# xtValveTimer.net
KiCad netlist of a schematic drawn in EasyEDA
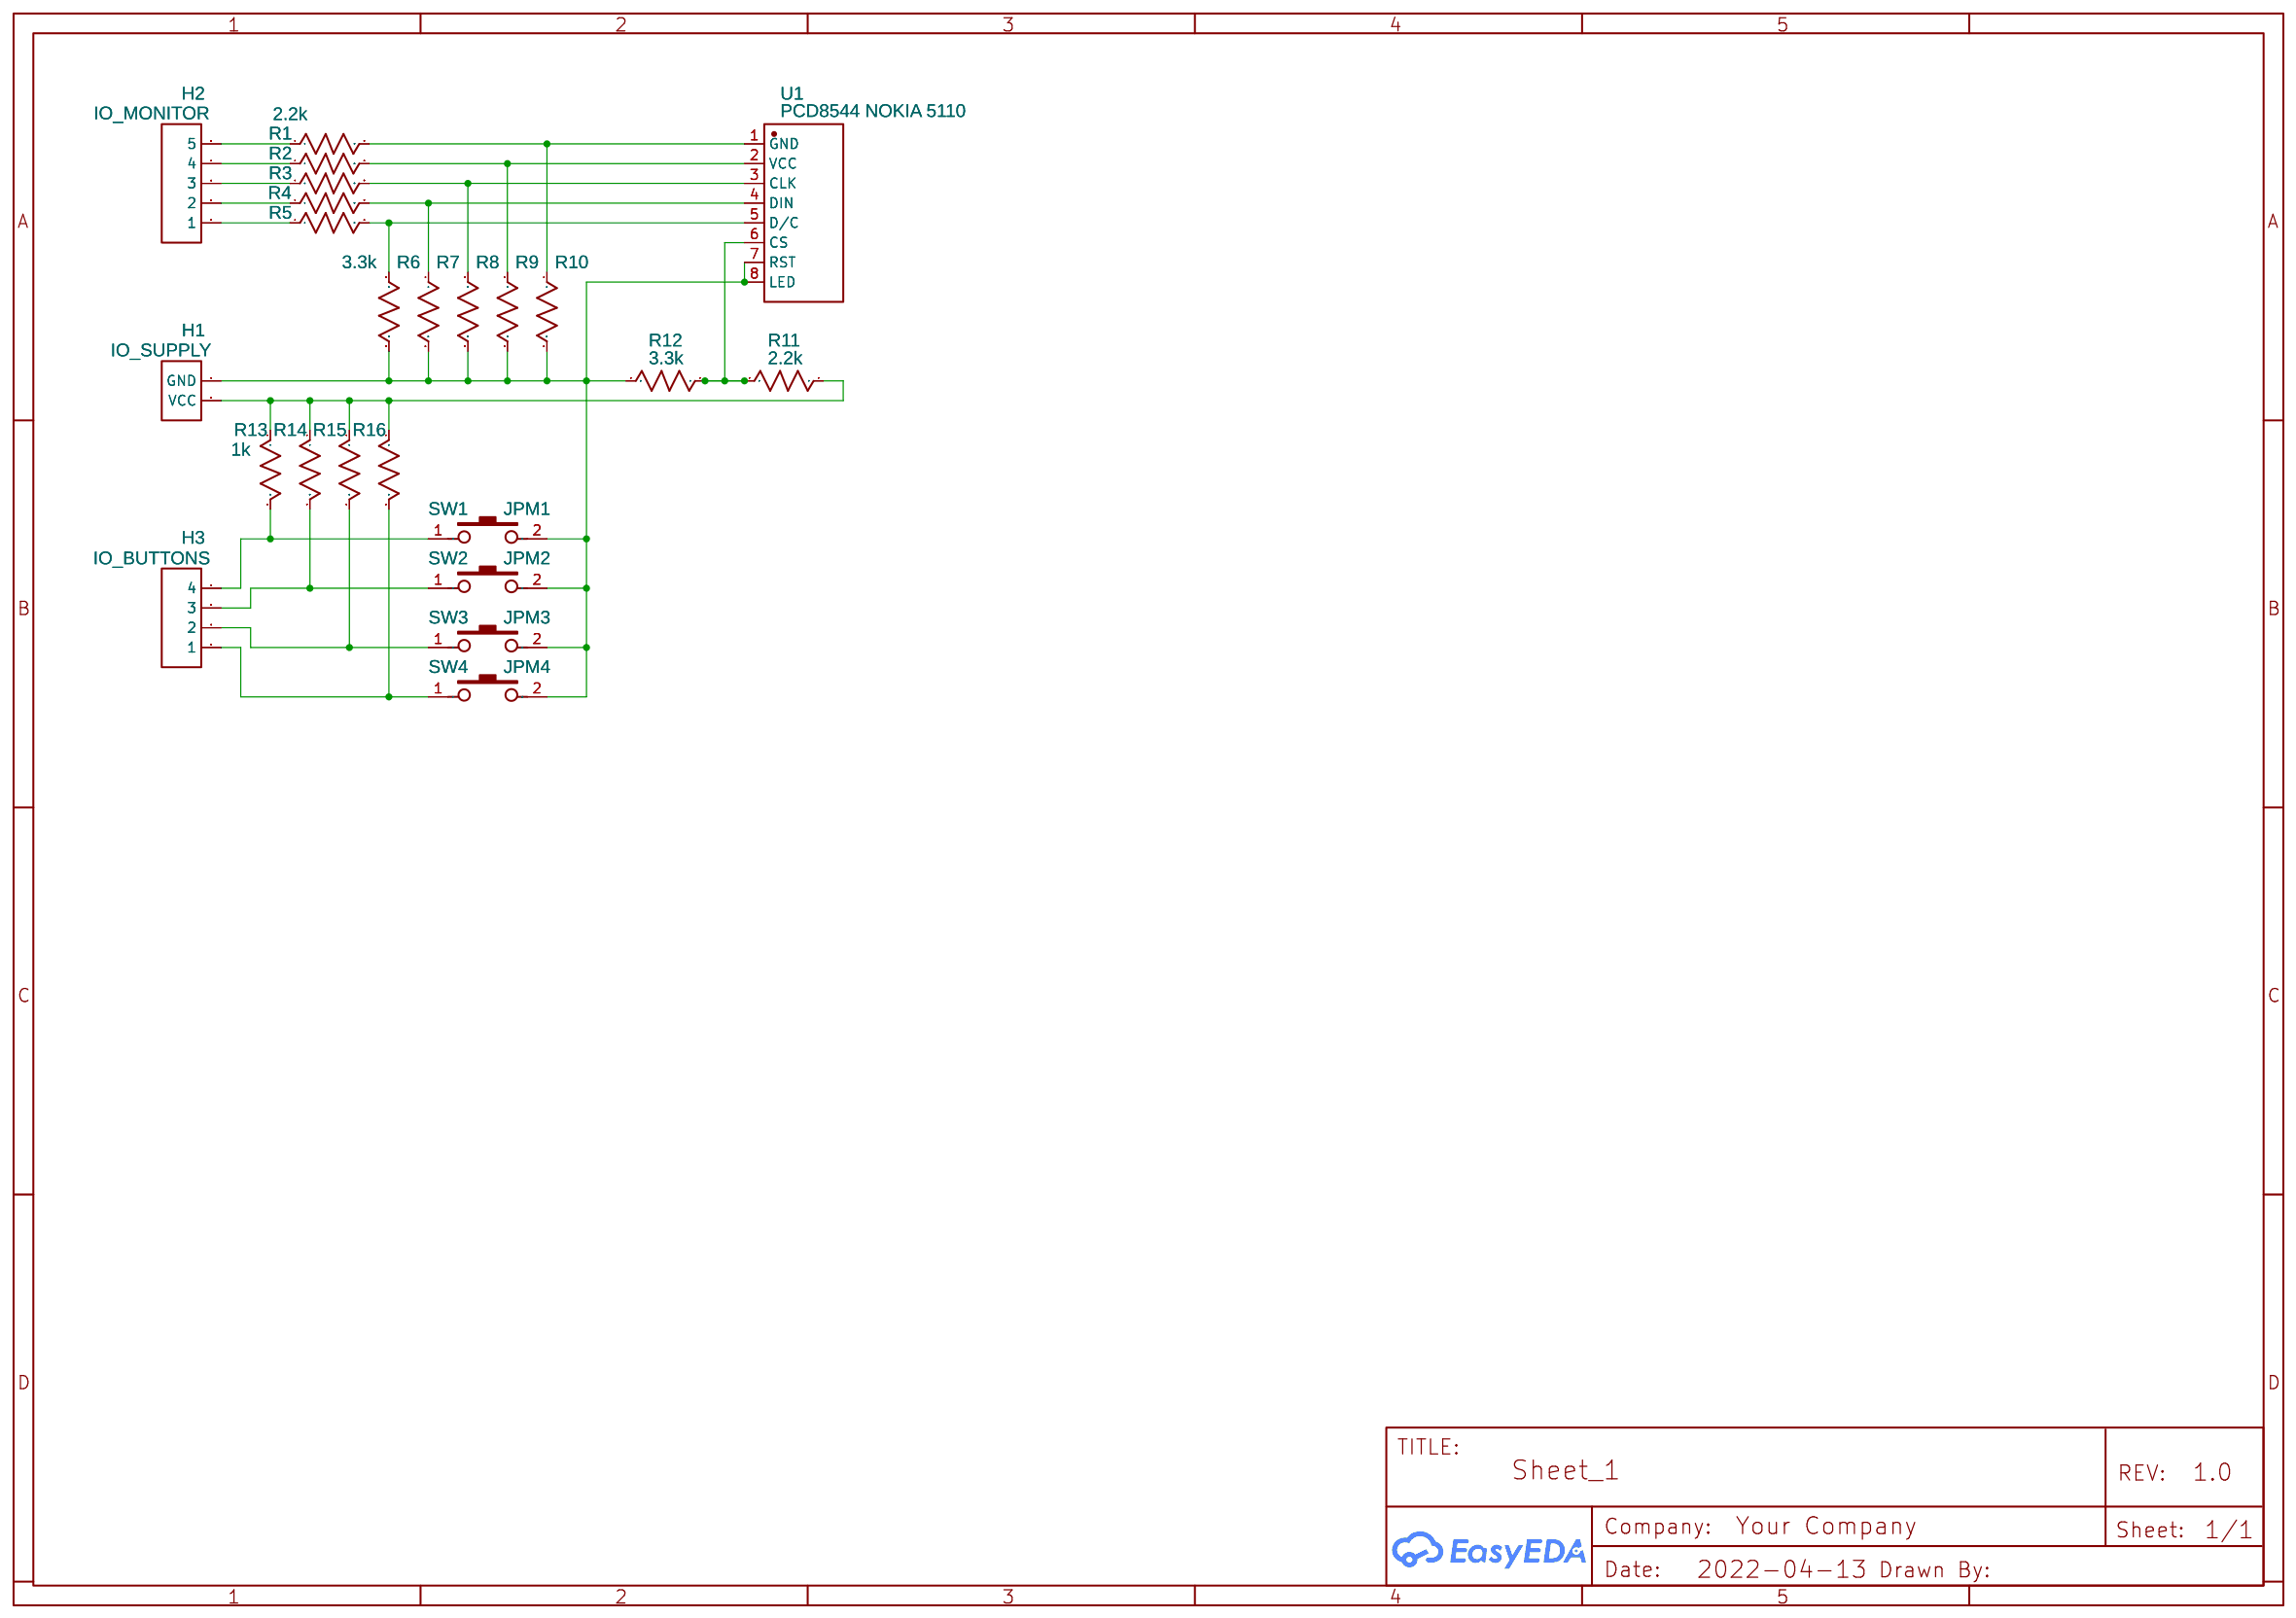
[diagram p0: schematic sheet]

(export (version "E")
  (design (tool "Eeschema 10.0.6"))
  (components
    (comp (ref "H1")
      (value "IO_SUPPLY")
      (fields (field (name "BOM_Supplier Part") "C49661"))
      (libsource (lib "") (part "HDR-F-2.54_1x2"))
    )
    (comp (ref "H2")
      (value "IO_MONITOR")
      (fields (field (name "BOM_Supplier Part") "C50950"))
      (libsource (lib "") (part "HDR-F-2.54_1x5"))
    )
    (comp (ref "H3")
      (value "IO_BUTTONS")
      (fields (field (name "BOM_Supplier Part") "C225501"))
      (libsource (lib "") (part "HDR-F-2.54_1x4"))
    )
    (comp (ref "R1") (value "2.2k") (libsource (lib "") (part "R_0603_US_2")))
    (comp (ref "R2") (value "1k") (libsource (lib "") (part "R_0603_US_2")))
    (comp (ref "R3") (value "1k") (libsource (lib "") (part "R_0603_US_2")))
    (comp (ref "R4") (value "1k") (libsource (lib "") (part "R_0603_US_2")))
    (comp (ref "R5") (value "1k") (libsource (lib "") (part "R_0603_US_2")))
    (comp (ref "R6") (value "3.3k") (libsource (lib "") (part "R_0603_US_1")))
    (comp (ref "R7") (value "3.3k") (libsource (lib "") (part "R_0603_US_1")))
    (comp (ref "R8") (value "3.3k") (libsource (lib "") (part "R_0603_US_1")))
    (comp (ref "R9") (value "3.3k") (libsource (lib "") (part "R_0603_US_1")))
    (comp (ref "R10") (value "3.3k") (libsource (lib "") (part "R_0603_US_1")))
    (comp (ref "R11") (value "2.2k") (libsource (lib "") (part "R_0603_US_3")))
    (comp (ref "R12") (value "3.3k") (libsource (lib "") (part "R_0603_US_3")))
    (comp (ref "R13") (value "1k") (libsource (lib "") (part "R_0603_US")))
    (comp (ref "R14") (value "1k") (libsource (lib "") (part "R_0603_US")))
    (comp (ref "R15") (value "1k") (libsource (lib "") (part "R_0603_US")))
    (comp (ref "R16") (value "1k") (libsource (lib "") (part "R_0603_US")))
    (comp (ref "SW1")
      (value "JPM1")
      (fields
        (field (name "BOM_Manufacturer Part") "JPM1040-2013FC")
        (field (name "BOM_Supplier Part") "C516061")
      )
      (libsource (lib "") (part "JPM1040-2013FC"))
    )
    (comp (ref "SW2")
      (value "JPM2")
      (fields
        (field (name "BOM_Manufacturer Part") "JPM1040-2013FC")
        (field (name "BOM_Supplier Part") "C516061")
      )
      (libsource (lib "") (part "JPM1040-2013FC"))
    )
    (comp (ref "SW3")
      (value "JPM3")
      (fields
        (field (name "BOM_Manufacturer Part") "JPM1040-2013FC")
        (field (name "BOM_Supplier Part") "C516061")
      )
      (libsource (lib "") (part "JPM1040-2013FC"))
    )
    (comp (ref "SW4")
      (value "JPM4")
      (fields
        (field (name "BOM_Manufacturer Part") "JPM1040-2013FC")
        (field (name "BOM_Supplier Part") "C516061")
      )
      (libsource (lib "") (part "JPM1040-2013FC"))
    )
    (comp (ref "U1") (value "PCD8544 NOKIA 5110") (libsource (lib "") (part "PCD8544 NOKIA 5110")))
  )
  (nets
    (net (code "1") (name "Net-(H1-GND)") (class "Default")
      (node (ref "H1") (pin "2") (pinfunction "GND_2") (pintype "input"))
      (node (ref "R10") (pin "2") (pinfunction "2_2") (pintype "unspecified"))
      (node (ref "R12") (pin "2") (pinfunction "2_2") (pintype "unspecified"))
      (node (ref "R6") (pin "2") (pinfunction "2_2") (pintype "unspecified"))
      (node (ref "R7") (pin "2") (pinfunction "2_2") (pintype "unspecified"))
      (node (ref "R8") (pin "2") (pinfunction "2_2") (pintype "unspecified"))
      (node (ref "R9") (pin "2") (pinfunction "2_2") (pintype "unspecified"))
      (node (ref "SW1") (pin "2") (pinfunction "2_2") (pintype "input"))
      (node (ref "SW2") (pin "2") (pinfunction "2_2") (pintype "input"))
      (node (ref "SW3") (pin "2") (pinfunction "2_2") (pintype "input"))
      (node (ref "SW4") (pin "2") (pinfunction "2_2") (pintype "input"))
      (node (ref "U1") (pin "7") (pinfunction "RST_7") (pintype "unspecified"))
      (node (ref "U1") (pin "8") (pinfunction "LED_8") (pintype "unspecified"))
    )
    (net (code "2") (name "Net-(H1-VCC)") (class "Default")
      (node (ref "H1") (pin "1") (pinfunction "VCC_1") (pintype "input"))
      (node (ref "R11") (pin "1") (pinfunction "1_1") (pintype "unspecified"))
      (node (ref "R13") (pin "1") (pinfunction "1_1") (pintype "unspecified"))
      (node (ref "R14") (pin "1") (pinfunction "1_1") (pintype "unspecified"))
      (node (ref "R15") (pin "1") (pinfunction "1_1") (pintype "unspecified"))
      (node (ref "R16") (pin "1") (pinfunction "1_1") (pintype "unspecified"))
    )
    (net (code "3") (name "Net-(H2-Pad1)") (class "Default")
      (node (ref "H2") (pin "1") (pinfunction "1_1") (pintype "unspecified"))
      (node (ref "R5") (pin "1") (pinfunction "1_1") (pintype "unspecified"))
    )
    (net (code "4") (name "Net-(H2-Pad2)") (class "Default")
      (node (ref "H2") (pin "2") (pinfunction "2_2") (pintype "unspecified"))
      (node (ref "R4") (pin "1") (pinfunction "1_1") (pintype "unspecified"))
    )
    (net (code "5") (name "Net-(H2-Pad3)") (class "Default")
      (node (ref "H2") (pin "3") (pinfunction "3_3") (pintype "unspecified"))
      (node (ref "R3") (pin "1") (pinfunction "1_1") (pintype "unspecified"))
    )
    (net (code "6") (name "Net-(H2-Pad4)") (class "Default")
      (node (ref "H2") (pin "4") (pinfunction "4_4") (pintype "unspecified"))
      (node (ref "R2") (pin "1") (pinfunction "1_1") (pintype "unspecified"))
    )
    (net (code "7") (name "Net-(H2-Pad5)") (class "Default")
      (node (ref "H2") (pin "5") (pinfunction "5_5") (pintype "unspecified"))
      (node (ref "R1") (pin "1") (pinfunction "1_1") (pintype "unspecified"))
    )
    (net (code "8") (name "Net-(H3-Pad1)") (class "Default")
      (node (ref "H3") (pin "1") (pinfunction "1_1") (pintype "unspecified"))
      (node (ref "R16") (pin "2") (pinfunction "2_2") (pintype "unspecified"))
      (node (ref "SW4") (pin "1") (pinfunction "1_1") (pintype "input"))
    )
    (net (code "9") (name "Net-(H3-Pad2)") (class "Default")
      (node (ref "H3") (pin "2") (pinfunction "2_2") (pintype "unspecified"))
      (node (ref "R15") (pin "2") (pinfunction "2_2") (pintype "unspecified"))
      (node (ref "SW3") (pin "1") (pinfunction "1_1") (pintype "input"))
    )
    (net (code "10") (name "Net-(H3-Pad3)") (class "Default")
      (node (ref "H3") (pin "3") (pinfunction "3_3") (pintype "unspecified"))
      (node (ref "R14") (pin "2") (pinfunction "2_2") (pintype "unspecified"))
      (node (ref "SW2") (pin "1") (pinfunction "1_1") (pintype "input"))
    )
    (net (code "11") (name "Net-(H3-Pad4)") (class "Default")
      (node (ref "H3") (pin "4") (pinfunction "4_4") (pintype "unspecified"))
      (node (ref "R13") (pin "2") (pinfunction "2_2") (pintype "unspecified"))
      (node (ref "SW1") (pin "1") (pinfunction "1_1") (pintype "input"))
    )
    (net (code "12") (name "Net-(U1-CLK)") (class "Default")
      (node (ref "R3") (pin "2") (pinfunction "2_2") (pintype "unspecified"))
      (node (ref "R8") (pin "1") (pinfunction "1_1") (pintype "unspecified"))
      (node (ref "U1") (pin "3") (pinfunction "CLK_3") (pintype "unspecified"))
    )
    (net (code "13") (name "Net-(U1-CS)") (class "Default")
      (node (ref "R11") (pin "2") (pinfunction "2_2") (pintype "unspecified"))
      (node (ref "R12") (pin "1") (pinfunction "1_1") (pintype "unspecified"))
      (node (ref "U1") (pin "6") (pinfunction "CS_6") (pintype "unspecified"))
    )
    (net (code "14") (name "Net-(U1-DIN)") (class "Default")
      (node (ref "R4") (pin "2") (pinfunction "2_2") (pintype "unspecified"))
      (node (ref "R7") (pin "1") (pinfunction "1_1") (pintype "unspecified"))
      (node (ref "U1") (pin "4") (pinfunction "DIN_4") (pintype "unspecified"))
    )
    (net (code "15") (name "Net-(U1-D{slash}C)") (class "Default")
      (node (ref "R5") (pin "2") (pinfunction "2_2") (pintype "unspecified"))
      (node (ref "R6") (pin "1") (pinfunction "1_1") (pintype "unspecified"))
      (node (ref "U1") (pin "5") (pinfunction "D/C_5") (pintype "unspecified"))
    )
    (net (code "16") (name "Net-(U1-GND)") (class "Default")
      (node (ref "R1") (pin "2") (pinfunction "2_2") (pintype "unspecified"))
      (node (ref "R10") (pin "1") (pinfunction "1_1") (pintype "unspecified"))
      (node (ref "U1") (pin "1") (pinfunction "GND_1") (pintype "unspecified"))
    )
    (net (code "17") (name "Net-(U1-VCC)") (class "Default")
      (node (ref "R2") (pin "2") (pinfunction "2_2") (pintype "unspecified"))
      (node (ref "R9") (pin "1") (pinfunction "1_1") (pintype "unspecified"))
      (node (ref "U1") (pin "2") (pinfunction "VCC_2") (pintype "unspecified"))
    )
  )
)
